# PCB_1.net
KiCad netlist of a schematic drawn in EAGLE
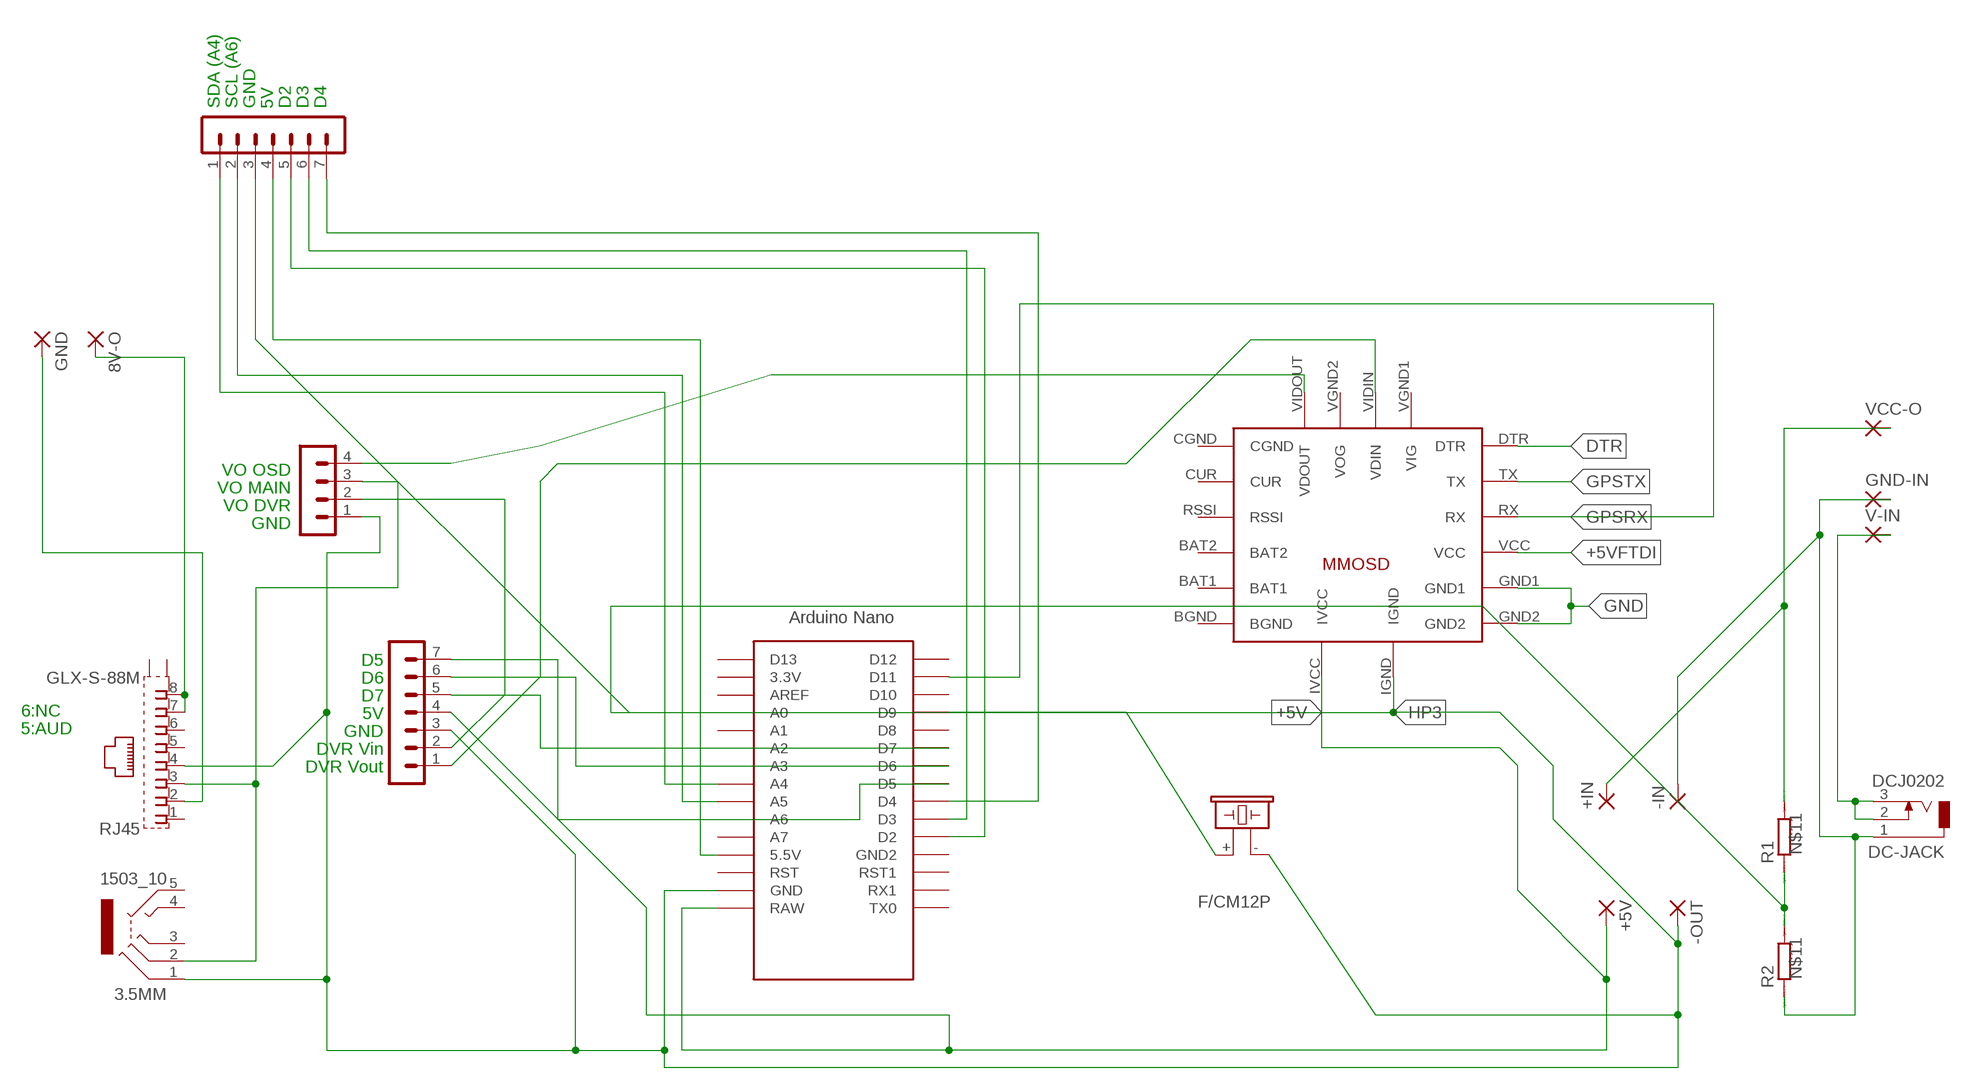
[diagram p0: schematic, sheet 1]

(export (version "E")
  (design (tool "Eeschema 10.0.6"))
  (components
    (comp (ref "+5V")
      (value "SMD2")
      (footprint "eagle-import:SMD1,27-2,54")
      (libsource (lib "eagle-import") (part "SMD2"))
    )
    (comp (ref "+IN")
      (value "SMD2")
      (footprint "eagle-import:SMD1,27-2,54")
      (libsource (lib "eagle-import") (part "SMD2"))
    )
    (comp (ref "-IN")
      (value "SMD2")
      (footprint "eagle-import:SMD1,27-2,54")
      (libsource (lib "eagle-import") (part "SMD2"))
    )
    (comp (ref "-OUT")
      (value "SMD2")
      (footprint "eagle-import:SMD1,27-2,54")
      (libsource (lib "eagle-import") (part "SMD2"))
    )
    (comp (ref "3.5MM")
      (value "1503_10")
      (footprint "eagle-import:1503_10")
      (libsource (lib "eagle-import") (part "1503_10"))
    )
    (comp (ref "8V-O")
      (value "2,54/1,1")
      (footprint "eagle-import:2,54_1,1")
      (libsource (lib "eagle-import") (part "2,54/1,1"))
    )
    (comp (ref "ADRUINO-NANO")
      (value "NANO")
      (footprint "eagle-import:NANO")
      (libsource (lib "eagle-import") (part "NANO"))
    )
    (comp (ref "BUZZ")
      (value "F/CM12P")
      (footprint "eagle-import:F_CM12P")
      (fields (field (name "SPICEPREFIX") "X"))
      (libsource (lib "eagle-import") (part "F/CM12P"))
    )
    (comp (ref "DC-JACK")
      (value "DCJ0202")
      (footprint "eagle-import:DCJ0202")
      (libsource (lib "eagle-import") (part "DCJ0202"))
    )
    (comp (ref "GND")
      (value "2,54/1,1")
      (footprint "eagle-import:2,54_1,1")
      (libsource (lib "eagle-import") (part "2,54/1,1"))
    )
    (comp (ref "GND-IN")
      (value "2,54/1,1")
      (footprint "eagle-import:2,54_1,1")
      (libsource (lib "eagle-import") (part "2,54/1,1"))
    )
    (comp (ref "IO1")
      (value "MA07-1")
      (footprint "eagle-import:MA07-1")
      (libsource (lib "eagle-import") (part "MA07-1"))
    )
    (comp (ref "IO2")
      (value "MA07-1")
      (footprint "eagle-import:MA07-1")
      (libsource (lib "eagle-import") (part "MA07-1"))
    )
    (comp (ref "IO3")
      (value "MA04-1")
      (footprint "eagle-import:MA04-1")
      (libsource (lib "eagle-import") (part "MA04-1"))
    )
    (comp (ref "MINIMOSD")
      (value "MICROMINIMOSDPWR")
      (footprint "eagle-import:MMOSDNVDVID")
      (libsource (lib "eagle-import") (part "MICROMINIMOSDPWR"))
    )
    (comp (ref "R1")
      (value "R0207/10")
      (footprint "eagle-import:0207_10")
      (libsource (lib "eagle-import") (part "R0207/10"))
    )
    (comp (ref "R2")
      (value "R0207/10")
      (footprint "eagle-import:0207_10")
      (libsource (lib "eagle-import") (part "R0207/10"))
    )
    (comp (ref "RJ45")
      (value "GLX-S-88M")
      (footprint "eagle-import:GLX-S-88M")
      (libsource (lib "eagle-import") (part "GLX-S-88M"))
    )
    (comp (ref "V-IN")
      (value "2,54/1,1")
      (footprint "eagle-import:2,54_1,1")
      (libsource (lib "eagle-import") (part "2,54/1,1"))
    )
    (comp (ref "VCC-O")
      (value "2,54/1,1")
      (footprint "eagle-import:2,54_1,1")
      (libsource (lib "eagle-import") (part "2,54/1,1"))
    )
  )
  (nets
    (net (code "1") (name "+5V") (class "Default")
      (node (ref "+5V") (pin "1") (pinfunction "P_1") (pintype "passive"))
      (node (ref "ADRUINO-NANO") (pin "RAW") (pinfunction "RAW_RAW") (pintype "bidirectional"))
      (node (ref "IO1") (pin "4") (pinfunction "4_4") (pintype "passive"))
      (node (ref "MINIMOSD") (pin "IVCC") (pinfunction "IVCC_IVCC") (pintype "power_in"))
    )
    (net (code "2") (name "+5VFTDI") (class "Default")
      (node (ref "MINIMOSD") (pin "VCC") (pinfunction "VCC_VCC") (pintype "power_in"))
    )
    (net (code "3") (name "/BAT1") (class "Default")
      (node (ref "MINIMOSD") (pin "BAT1") (pinfunction "BAT1_BAT1") (pintype "power_in"))
    )
    (net (code "4") (name "/BAT2") (class "Default")
      (node (ref "MINIMOSD") (pin "BAT2") (pinfunction "BAT2_BAT2") (pintype "power_in"))
    )
    (net (code "5") (name "/BGND") (class "Default")
      (node (ref "MINIMOSD") (pin "BGND") (pinfunction "BGND_BGND") (pintype "power_in"))
    )
    (net (code "6") (name "/CGND") (class "Default")
      (node (ref "MINIMOSD") (pin "CGND") (pinfunction "CGND_CGND") (pintype "power_in"))
    )
    (net (code "7") (name "/N$11") (class "Default")
      (node (ref "-IN") (pin "1") (pinfunction "P_1") (pintype "passive"))
      (node (ref "DC-JACK") (pin "1") (pinfunction "1_1") (pintype "passive"))
      (node (ref "GND-IN") (pin "1") (pinfunction "P_1") (pintype "passive"))
      (node (ref "R2") (pin "1") (pinfunction "1_1") (pintype "passive"))
    )
    (net (code "8") (name "DTR") (class "Default")
      (node (ref "MINIMOSD") (pin "DTR") (pinfunction "DTR_DTR") (pintype "bidirectional"))
    )
    (net (code "9") (name "GND") (class "Default")
      (node (ref "MINIMOSD") (pin "GND1") (pinfunction "GND1_GND1") (pintype "power_in"))
      (node (ref "MINIMOSD") (pin "GND2") (pinfunction "GND2_GND2") (pintype "power_in"))
    )
    (net (code "10") (name "GPSRX") (class "Default")
      (node (ref "ADRUINO-NANO") (pin "D11") (pinfunction "D11_D11") (pintype "bidirectional"))
      (node (ref "MINIMOSD") (pin "RX") (pinfunction "RX_RX") (pintype "input"))
    )
    (net (code "11") (name "GPSTX") (class "Default")
      (node (ref "MINIMOSD") (pin "TX") (pinfunction "TX_TX") (pintype "output"))
    )
    (net (code "12") (name "HP3") (class "Default")
      (node (ref "-OUT") (pin "1") (pinfunction "P_1") (pintype "passive"))
      (node (ref "3.5MM") (pin "1") (pinfunction "1_1") (pintype "passive"))
      (node (ref "ADRUINO-NANO") (pin "GND") (pinfunction "GND_GND") (pintype "bidirectional"))
      (node (ref "BUZZ") (pin "-") (pinfunction "2_-") (pintype "passive"))
      (node (ref "IO1") (pin "3") (pinfunction "3_3") (pintype "passive"))
      (node (ref "IO2") (pin "3") (pinfunction "3_3") (pintype "passive"))
      (node (ref "IO3") (pin "1") (pinfunction "1_1") (pintype "passive"))
      (node (ref "MINIMOSD") (pin "IGND") (pinfunction "IGND_IGND") (pintype "power_in"))
      (node (ref "RJ45") (pin "4") (pinfunction "4_4") (pintype "passive"))
    )
    (net (code "13") (name "Net-(+IN-P)") (class "Default")
      (node (ref "+IN") (pin "1") (pinfunction "P_1") (pintype "passive"))
      (node (ref "R1") (pin "2") (pinfunction "2_2") (pintype "passive"))
      (node (ref "VCC-O") (pin "1") (pinfunction "P_1") (pintype "passive"))
    )
    (net (code "14") (name "Net-(3.5MM-Pad2)") (class "Default")
      (node (ref "3.5MM") (pin "2") (pinfunction "2_2") (pintype "passive"))
      (node (ref "IO3") (pin "3") (pinfunction "3_3") (pintype "passive"))
      (node (ref "RJ45") (pin "3") (pinfunction "3_3") (pintype "passive"))
    )
    (net (code "15") (name "Net-(8V-O-P)") (class "Default")
      (node (ref "8V-O") (pin "1") (pinfunction "P_1") (pintype "passive"))
      (node (ref "RJ45") (pin "7") (pinfunction "7_7") (pintype "passive"))
      (node (ref "RJ45") (pin "8") (pinfunction "8_8") (pintype "passive"))
    )
    (net (code "16") (name "Net-(ADRUINO-NANO-5.5V)") (class "Default")
      (node (ref "ADRUINO-NANO") (pin "5V") (pinfunction "5.5V_5V") (pintype "bidirectional"))
      (node (ref "IO2") (pin "4") (pinfunction "4_4") (pintype "passive"))
    )
    (net (code "17") (name "Net-(ADRUINO-NANO-PadA0)") (class "Default")
      (node (ref "ADRUINO-NANO") (pin "A0") (pinfunction "A0_A0") (pintype "bidirectional"))
      (node (ref "R1") (pin "1") (pinfunction "1_1") (pintype "passive"))
      (node (ref "R2") (pin "2") (pinfunction "2_2") (pintype "passive"))
    )
    (net (code "18") (name "Net-(ADRUINO-NANO-PadA4)") (class "Default")
      (node (ref "ADRUINO-NANO") (pin "A4") (pinfunction "A4_A4") (pintype "bidirectional"))
      (node (ref "IO2") (pin "1") (pinfunction "1_1") (pintype "passive"))
    )
    (net (code "19") (name "Net-(ADRUINO-NANO-PadA5)") (class "Default")
      (node (ref "ADRUINO-NANO") (pin "A5") (pinfunction "A5_A5") (pintype "bidirectional"))
      (node (ref "IO2") (pin "2") (pinfunction "2_2") (pintype "passive"))
    )
    (net (code "20") (name "Net-(ADRUINO-NANO-PadD2)") (class "Default")
      (node (ref "ADRUINO-NANO") (pin "D2") (pinfunction "D2_D2") (pintype "bidirectional"))
      (node (ref "IO2") (pin "5") (pinfunction "5_5") (pintype "passive"))
    )
    (net (code "21") (name "Net-(ADRUINO-NANO-PadD3)") (class "Default")
      (node (ref "ADRUINO-NANO") (pin "D3") (pinfunction "D3_D3") (pintype "bidirectional"))
      (node (ref "IO2") (pin "6") (pinfunction "6_6") (pintype "passive"))
    )
    (net (code "22") (name "Net-(ADRUINO-NANO-PadD4)") (class "Default")
      (node (ref "ADRUINO-NANO") (pin "D4") (pinfunction "D4_D4") (pintype "bidirectional"))
      (node (ref "IO2") (pin "7") (pinfunction "7_7") (pintype "passive"))
    )
    (net (code "23") (name "Net-(ADRUINO-NANO-PadD5)") (class "Default")
      (node (ref "ADRUINO-NANO") (pin "D5") (pinfunction "D5_D5") (pintype "bidirectional"))
      (node (ref "IO1") (pin "7") (pinfunction "7_7") (pintype "passive"))
    )
    (net (code "24") (name "Net-(ADRUINO-NANO-PadD6)") (class "Default")
      (node (ref "ADRUINO-NANO") (pin "D6") (pinfunction "D6_D6") (pintype "bidirectional"))
      (node (ref "IO1") (pin "6") (pinfunction "6_6") (pintype "passive"))
    )
    (net (code "25") (name "Net-(ADRUINO-NANO-PadD7)") (class "Default")
      (node (ref "ADRUINO-NANO") (pin "D7") (pinfunction "D7_D7") (pintype "bidirectional"))
      (node (ref "IO1") (pin "5") (pinfunction "5_5") (pintype "passive"))
    )
    (net (code "26") (name "Net-(BUZZ-1)") (class "Default")
      (node (ref "ADRUINO-NANO") (pin "D9") (pinfunction "D9_D9") (pintype "bidirectional"))
      (node (ref "BUZZ") (pin "+") (pinfunction "1_+") (pintype "passive"))
    )
    (net (code "27") (name "Net-(GND-P)") (class "Default")
      (node (ref "GND") (pin "1") (pinfunction "P_1") (pintype "passive"))
      (node (ref "RJ45") (pin "2") (pinfunction "2_2") (pintype "passive"))
    )
    (net (code "28") (name "Net-(IO1-Pad2)") (class "Default")
      (node (ref "IO1") (pin "2") (pinfunction "2_2") (pintype "passive"))
      (node (ref "IO3") (pin "2") (pinfunction "2_2") (pintype "passive"))
    )
    (net (code "29") (name "Net-(MINIMOSD-VDIN)") (class "Default")
      (node (ref "IO1") (pin "1") (pinfunction "1_1") (pintype "passive"))
      (node (ref "MINIMOSD") (pin "VIDIN") (pinfunction "VDIN_VIDIN") (pintype "input"))
    )
    (net (code "30") (name "Net-(MINIMOSD-VDOUT)") (class "Default")
      (node (ref "IO3") (pin "4") (pinfunction "4_4") (pintype "passive"))
      (node (ref "MINIMOSD") (pin "VIDOUT") (pinfunction "VDOUT_VIDOUT") (pintype "output"))
    )
    (net (code "31") (name "Net-(V-IN-P)") (class "Default")
      (node (ref "DC-JACK") (pin "2") (pinfunction "2_2") (pintype "passive"))
      (node (ref "DC-JACK") (pin "3") (pinfunction "3_3") (pintype "passive"))
      (node (ref "V-IN") (pin "1") (pinfunction "P_1") (pintype "passive"))
    )
    (net (code "32") (name "unconnected-(3.5MM-Pad3)") (class "Default")
      (node (ref "3.5MM") (pin "3") (pinfunction "3_3") (pintype "passive"))
    )
    (net (code "33") (name "unconnected-(3.5MM-Pad4)") (class "Default")
      (node (ref "3.5MM") (pin "4") (pinfunction "4_4") (pintype "passive"))
    )
    (net (code "34") (name "unconnected-(3.5MM-Pad5)") (class "Default")
      (node (ref "3.5MM") (pin "5") (pinfunction "5_5") (pintype "passive"))
    )
    (net (code "35") (name "unconnected-(ADRUINO-NANO-GND2-PadGND1)") (class "Default")
      (node (ref "ADRUINO-NANO") (pin "GND1") (pinfunction "GND2_GND1") (pintype "bidirectional"))
    )
    (net (code "36") (name "unconnected-(ADRUINO-NANO-Pad3.3V)") (class "Default")
      (node (ref "ADRUINO-NANO") (pin "3.3V") (pinfunction "3.3V_3.3V") (pintype "bidirectional"))
    )
    (net (code "37") (name "unconnected-(ADRUINO-NANO-PadA1)") (class "Default")
      (node (ref "ADRUINO-NANO") (pin "A1") (pinfunction "A1_A1") (pintype "bidirectional"))
    )
    (net (code "38") (name "unconnected-(ADRUINO-NANO-PadA2)") (class "Default")
      (node (ref "ADRUINO-NANO") (pin "A2") (pinfunction "A2_A2") (pintype "bidirectional"))
    )
    (net (code "39") (name "unconnected-(ADRUINO-NANO-PadA3)") (class "Default")
      (node (ref "ADRUINO-NANO") (pin "A3") (pinfunction "A3_A3") (pintype "bidirectional"))
    )
    (net (code "40") (name "unconnected-(ADRUINO-NANO-PadA6)") (class "Default")
      (node (ref "ADRUINO-NANO") (pin "A6") (pinfunction "A6_A6") (pintype "bidirectional"))
    )
    (net (code "41") (name "unconnected-(ADRUINO-NANO-PadA7)") (class "Default")
      (node (ref "ADRUINO-NANO") (pin "A7") (pinfunction "A7_A7") (pintype "bidirectional"))
    )
    (net (code "42") (name "unconnected-(ADRUINO-NANO-PadAREF)") (class "Default")
      (node (ref "ADRUINO-NANO") (pin "AREF") (pinfunction "AREF_AREF") (pintype "bidirectional"))
    )
    (net (code "43") (name "unconnected-(ADRUINO-NANO-PadD8)") (class "Default")
      (node (ref "ADRUINO-NANO") (pin "D8") (pinfunction "D8_D8") (pintype "bidirectional"))
    )
    (net (code "44") (name "unconnected-(ADRUINO-NANO-PadD10)") (class "Default")
      (node (ref "ADRUINO-NANO") (pin "D10") (pinfunction "D10_D10") (pintype "bidirectional"))
    )
    (net (code "45") (name "unconnected-(ADRUINO-NANO-PadD12)") (class "Default")
      (node (ref "ADRUINO-NANO") (pin "D12") (pinfunction "D12_D12") (pintype "bidirectional"))
    )
    (net (code "46") (name "unconnected-(ADRUINO-NANO-PadD13)") (class "Default")
      (node (ref "ADRUINO-NANO") (pin "D13") (pinfunction "D13_D13") (pintype "bidirectional"))
    )
    (net (code "47") (name "unconnected-(ADRUINO-NANO-PadICSP1)") (class "Default")
      (node (ref "ADRUINO-NANO") (pin "ICSP1") (pinfunction "ICSP1_ICSP1") (pintype "bidirectional"))
    )
    (net (code "48") (name "unconnected-(ADRUINO-NANO-PadICSP2)") (class "Default")
      (node (ref "ADRUINO-NANO") (pin "ICSP2") (pinfunction "ICSP2_ICSP2") (pintype "bidirectional"))
    )
    (net (code "49") (name "unconnected-(ADRUINO-NANO-PadICSP3)") (class "Default")
      (node (ref "ADRUINO-NANO") (pin "ICSP3") (pinfunction "ICSP3_ICSP3") (pintype "bidirectional"))
    )
    (net (code "50") (name "unconnected-(ADRUINO-NANO-PadICSP4)") (class "Default")
      (node (ref "ADRUINO-NANO") (pin "ICSP4") (pinfunction "ICSP4_ICSP4") (pintype "bidirectional"))
    )
    (net (code "51") (name "unconnected-(ADRUINO-NANO-PadICSP5)") (class "Default")
      (node (ref "ADRUINO-NANO") (pin "ICSP5") (pinfunction "ICSP5_ICSP5") (pintype "bidirectional"))
    )
    (net (code "52") (name "unconnected-(ADRUINO-NANO-PadICSP6)") (class "Default")
      (node (ref "ADRUINO-NANO") (pin "ICSP6") (pinfunction "ICSP6_ICSP6") (pintype "bidirectional"))
    )
    (net (code "53") (name "unconnected-(ADRUINO-NANO-PadRST)") (class "Default")
      (node (ref "ADRUINO-NANO") (pin "RST") (pinfunction "RST_RST") (pintype "bidirectional"))
    )
    (net (code "54") (name "unconnected-(ADRUINO-NANO-PadRST1)") (class "Default")
      (node (ref "ADRUINO-NANO") (pin "RST1") (pinfunction "RST1_RST1") (pintype "bidirectional"))
    )
    (net (code "55") (name "unconnected-(ADRUINO-NANO-PadRX1)") (class "Default")
      (node (ref "ADRUINO-NANO") (pin "RX1") (pinfunction "RX1_RX1") (pintype "bidirectional"))
    )
    (net (code "56") (name "unconnected-(ADRUINO-NANO-PadTX0)") (class "Default")
      (node (ref "ADRUINO-NANO") (pin "TX0") (pinfunction "TX0_TX0") (pintype "bidirectional"))
    )
    (net (code "57") (name "unconnected-(MINIMOSD-PadCUR)") (class "Default")
      (node (ref "MINIMOSD") (pin "CUR") (pinfunction "CUR_CUR") (pintype "bidirectional"))
    )
    (net (code "58") (name "unconnected-(MINIMOSD-PadRSSI)") (class "Default")
      (node (ref "MINIMOSD") (pin "RSSI") (pinfunction "RSSI_RSSI") (pintype "bidirectional"))
    )
    (net (code "59") (name "unconnected-(MINIMOSD-VIG-PadVGND1)") (class "Default")
      (node (ref "MINIMOSD") (pin "VGND1") (pinfunction "VIG_VGND1") (pintype "input"))
    )
    (net (code "60") (name "unconnected-(MINIMOSD-VOG-PadVGND2)") (class "Default")
      (node (ref "MINIMOSD") (pin "VGND2") (pinfunction "VOG_VGND2") (pintype "output"))
    )
    (net (code "61") (name "unconnected-(RJ45-Pad1)") (class "Default")
      (node (ref "RJ45") (pin "1") (pinfunction "1_1") (pintype "passive"))
    )
    (net (code "62") (name "unconnected-(RJ45-Pad5)") (class "Default")
      (node (ref "RJ45") (pin "5") (pinfunction "5_5") (pintype "passive"))
    )
    (net (code "63") (name "unconnected-(RJ45-Pad6)") (class "Default")
      (node (ref "RJ45") (pin "6") (pinfunction "6_6") (pintype "passive"))
    )
    (net (code "64") (name "unconnected-(RJ45-PadS1)") (class "Default")
      (node (ref "RJ45") (pin "S1") (pinfunction "S1_S1") (pintype "passive"))
    )
    (net (code "65") (name "unconnected-(RJ45-PadS2)") (class "Default")
      (node (ref "RJ45") (pin "S2") (pinfunction "S2_S2") (pintype "passive"))
    )
  )
)
